# 08_Peripherals.net
KiCad netlist of a schematic drawn in Altium Designer
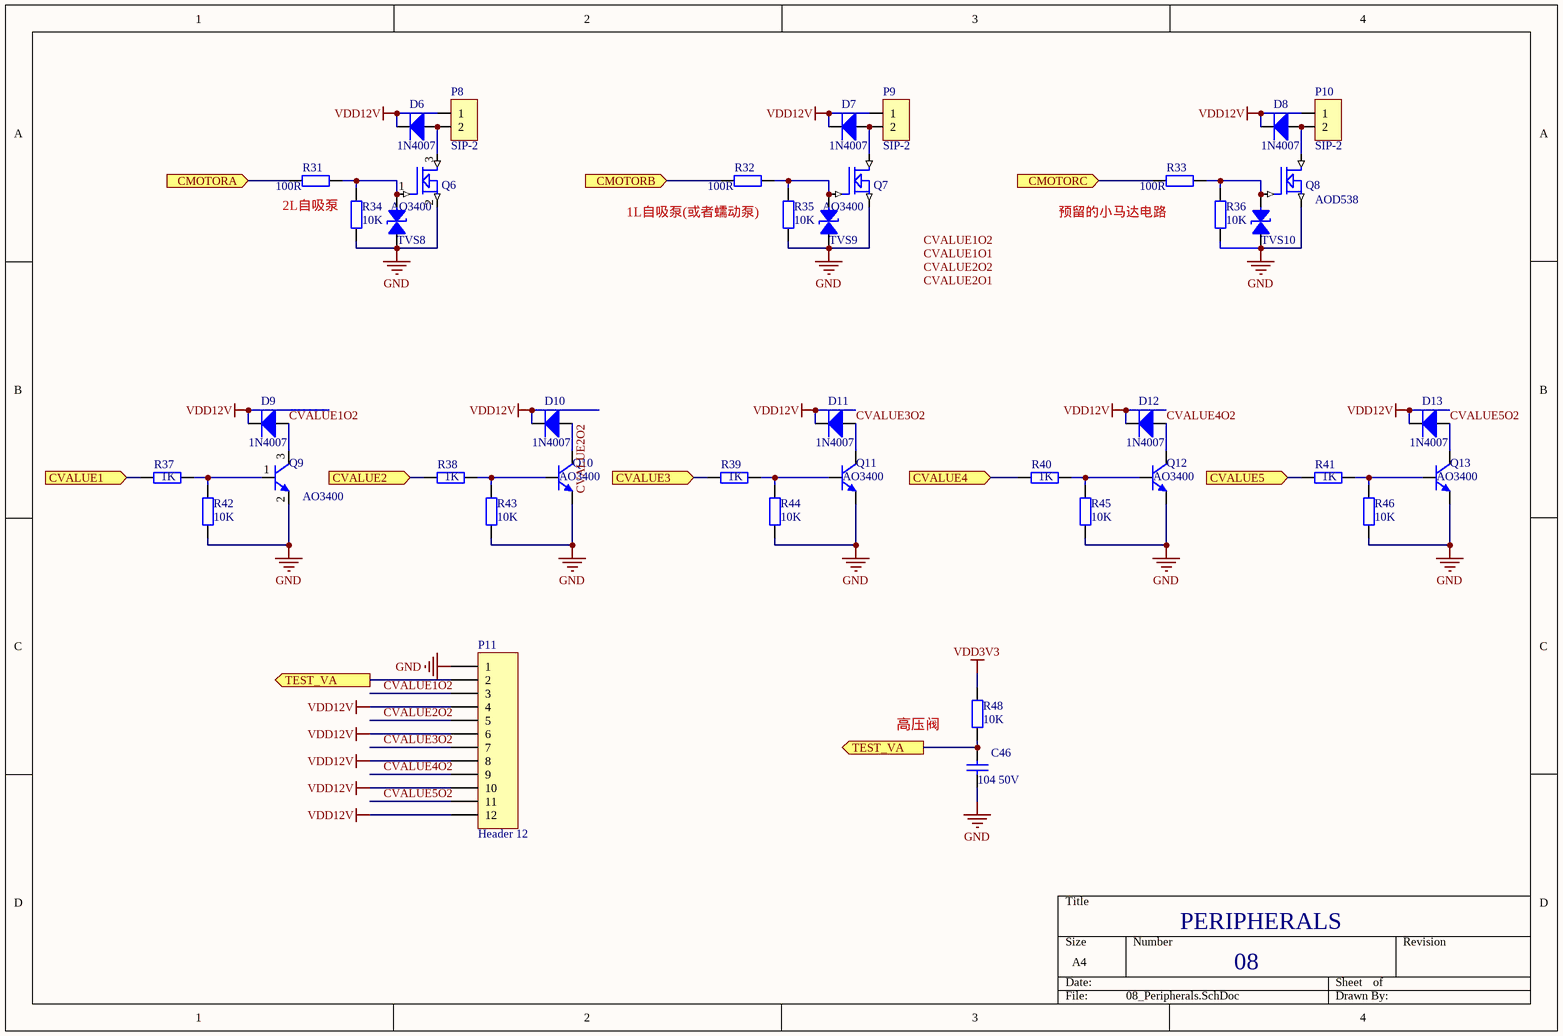
[diagram p0: 08_Peripherals.SchDoc]

(export (version "E")
  (design (tool "Eeschema 10.0.6"))
  (components
    (comp (ref "C46")
      (value "104 50V")
      (footprint "SMD-0603C")
      (description "贴片电容 10%")
      (libsource (lib "XiaoyI") (part "CAP4"))
    )
    (comp (ref "D6")
      (value "1N4007")
      (footprint "DO-214-AC")
      (description "贴片二极管")
      (libsource (lib "XiaoyI") (part "DIODE2"))
    )
    (comp (ref "D7")
      (value "1N4007")
      (footprint "DO-214-AC")
      (description "贴片二极管")
      (libsource (lib "XiaoyI") (part "DIODE2"))
    )
    (comp (ref "D8")
      (value "1N4007")
      (footprint "DO-214-AC")
      (description "贴片二极管")
      (libsource (lib "XiaoyI") (part "DIODE2"))
    )
    (comp (ref "D9")
      (value "1N4007")
      (footprint "DO-214-AC")
      (description "贴片二极管")
      (libsource (lib "XiaoyI") (part "DIODE2"))
    )
    (comp (ref "D10")
      (value "1N4007")
      (footprint "DO-214-AC")
      (description "贴片二极管")
      (libsource (lib "XiaoyI") (part "DIODE2"))
    )
    (comp (ref "D11")
      (value "1N4007")
      (footprint "DO-214-AC")
      (description "贴片二极管")
      (libsource (lib "XiaoyI") (part "DIODE2"))
    )
    (comp (ref "D12")
      (value "1N4007")
      (footprint "DO-214-AC")
      (description "贴片二极管")
      (libsource (lib "XiaoyI") (part "DIODE2"))
    )
    (comp (ref "D13")
      (value "1N4007")
      (footprint "DO-214-AC")
      (description "贴片二极管")
      (libsource (lib "XiaoyI") (part "DIODE2"))
    )
    (comp (ref "P8")
      (value "SIP-2")
      (footprint "SIP-2A")
      (description "XH2.54 2P 立贴")
      (libsource (lib "XiaoyI") (part "SIP-2"))
    )
    (comp (ref "P9")
      (value "SIP-2")
      (footprint "SIP-2A")
      (description "XH2.54 2P 立贴")
      (libsource (lib "XiaoyI") (part "SIP-2"))
    )
    (comp (ref "P10")
      (value "SIP-2")
      (footprint "VH-AW-3.96*2P")
      (description "XH2.54 2P 立贴")
      (libsource (lib "XiaoyI") (part "SIP-2"))
    )
    (comp (ref "P11")
      (value "Header 12")
      (footprint "12X2.54MMZ")
      (description "Header, 12-Pin")
      (fields (field (name "PUBLISHER") "Altium Limited"))
      (libsource (lib "Miscellaneous Connectors") (part "Header 12"))
    )
    (comp (ref "Q6")
      (value "AO3400")
      (footprint "SOT-23")
      (description "MOSFET N")
      (libsource (lib "XiaoyI") (part "MOSFET N"))
    )
    (comp (ref "Q7")
      (value "AO3400")
      (footprint "SOT-23")
      (description "MOSFET N")
      (libsource (lib "") (part "MOSFET N_1"))
    )
    (comp (ref "Q8")
      (value "AOD538")
      (footprint "TO252")
      (description "MOSFET N")
      (libsource (lib "") (part "MOSFET N_1"))
    )
    (comp (ref "Q9")
      (value "AO3400")
      (footprint "SOT-23")
      (description "三极管")
      (libsource (lib "XiaoyI") (part "NPN-1"))
    )
    (comp (ref "Q10")
      (value "AO3400")
      (footprint "SOT-23")
      (description "三极管")
      (libsource (lib "") (part "NPN-1_1"))
    )
    (comp (ref "Q11")
      (value "AO3400")
      (footprint "SOT-23")
      (description "三极管")
      (libsource (lib "") (part "NPN-1_1"))
    )
    (comp (ref "Q12")
      (value "AO3400")
      (footprint "SOT-23")
      (description "三极管")
      (libsource (lib "") (part "NPN-1_1"))
    )
    (comp (ref "Q13")
      (value "AO3400")
      (footprint "SOT-23")
      (description "三极管")
      (libsource (lib "") (part "NPN-1_1"))
    )
    (comp (ref "R31")
      (value "100R")
      (footprint "SMD-0603")
      (description "贴片电阻 5%")
      (libsource (lib "XiaoyI") (part "RES-SOP"))
    )
    (comp (ref "R32")
      (value "100R")
      (footprint "SMD-0603")
      (description "贴片电阻 5%")
      (libsource (lib "XiaoyI") (part "RES-SOP"))
    )
    (comp (ref "R33")
      (value "100R")
      (footprint "SMD-0603")
      (description "贴片电阻 5%")
      (libsource (lib "XiaoyI") (part "RES-SOP"))
    )
    (comp (ref "R34")
      (value "10K")
      (footprint "SMD-0603")
      (description "贴片电阻 5%")
      (libsource (lib "") (part "RES-SOP_1"))
    )
    (comp (ref "R35")
      (value "10K")
      (footprint "SMD-0603")
      (description "贴片电阻 5%")
      (libsource (lib "") (part "RES-SOP_1"))
    )
    (comp (ref "R36")
      (value "10K")
      (footprint "SMD-0603")
      (description "贴片电阻 5%")
      (libsource (lib "") (part "RES-SOP_1"))
    )
    (comp (ref "R37")
      (value "1K")
      (footprint "SMD-0603")
      (description "贴片电阻 5%")
      (libsource (lib "XiaoyI") (part "RES-SOP"))
    )
    (comp (ref "R38")
      (value "1K")
      (footprint "SMD-0603")
      (description "贴片电阻 5%")
      (libsource (lib "XiaoyI") (part "RES-SOP"))
    )
    (comp (ref "R39")
      (value "1K")
      (footprint "SMD-0603")
      (description "贴片电阻 5%")
      (libsource (lib "XiaoyI") (part "RES-SOP"))
    )
    (comp (ref "R40")
      (value "1K")
      (footprint "SMD-0603")
      (description "贴片电阻 5%")
      (libsource (lib "XiaoyI") (part "RES-SOP"))
    )
    (comp (ref "R41")
      (value "1K")
      (footprint "SMD-0603")
      (description "贴片电阻 5%")
      (libsource (lib "XiaoyI") (part "RES-SOP"))
    )
    (comp (ref "R42")
      (value "10K")
      (footprint "SMD-0603")
      (description "贴片电阻 5%")
      (libsource (lib "") (part "RES-SOP_1"))
    )
    (comp (ref "R43")
      (value "10K")
      (footprint "SMD-0603")
      (description "贴片电阻 5%")
      (libsource (lib "") (part "RES-SOP_1"))
    )
    (comp (ref "R44")
      (value "10K")
      (footprint "SMD-0603")
      (description "贴片电阻 5%")
      (libsource (lib "") (part "RES-SOP_1"))
    )
    (comp (ref "R45")
      (value "10K")
      (footprint "SMD-0603")
      (description "贴片电阻 5%")
      (libsource (lib "") (part "RES-SOP_1"))
    )
    (comp (ref "R46")
      (value "10K")
      (footprint "SMD-0603")
      (description "贴片电阻 5%")
      (libsource (lib "") (part "RES-SOP_1"))
    )
    (comp (ref "R48")
      (value "10K")
      (footprint "SMD-0603")
      (description "贴片电阻 5%")
      (libsource (lib "") (part "RES-SOP_2"))
    )
    (comp (ref "TVS8")
      (value "ESD5Z5.0CT1G")
      (footprint "SOD-523")
      (description "TVS")
      (libsource (lib "XiaoyI") (part "TVS-1"))
    )
    (comp (ref "TVS9")
      (value "ESD5Z5.0CT1G")
      (footprint "SOD-523")
      (description "TVS")
      (libsource (lib "XiaoyI") (part "TVS-1"))
    )
    (comp (ref "TVS10")
      (value "ESD5Z5.0CT1G")
      (footprint "SOD-523")
      (description "TVS")
      (libsource (lib "XiaoyI") (part "TVS-1"))
    )
  )
  (nets
    (net (code "1") (name "/CMOTORA") (class "Default")
      (node (ref "R31") (pin "2") (pinfunction "2_2") (pintype "passive"))
    )
    (net (code "2") (name "/CMOTORB") (class "Default")
      (node (ref "R32") (pin "2") (pinfunction "2_2") (pintype "passive"))
    )
    (net (code "3") (name "/CMOTORC") (class "Default")
      (node (ref "R33") (pin "2") (pinfunction "2_2") (pintype "passive"))
    )
    (net (code "4") (name "/CVALUE1") (class "Default")
      (node (ref "R37") (pin "2") (pinfunction "2_2") (pintype "passive"))
    )
    (net (code "6") (name "/CVALUE1O2") (class "Default")
      (node (ref "D9") (pin "1") (pinfunction "A_1") (pintype "passive"))
      (node (ref "P11") (pin "3") (pinfunction "3_3") (pintype "passive"))
      (node (ref "Q9") (pin "3") (pinfunction "C_3") (pintype "passive"))
    )
    (net (code "7") (name "/CVALUE2") (class "Default")
      (node (ref "R38") (pin "2") (pinfunction "2_2") (pintype "passive"))
    )
    (net (code "9") (name "/CVALUE2O2") (class "Default")
      (node (ref "D10") (pin "1") (pinfunction "A_1") (pintype "passive"))
      (node (ref "P11") (pin "5") (pinfunction "5_5") (pintype "passive"))
      (node (ref "Q10") (pin "3") (pinfunction "C_3") (pintype "passive"))
    )
    (net (code "10") (name "/CVALUE3") (class "Default")
      (node (ref "R39") (pin "2") (pinfunction "2_2") (pintype "passive"))
    )
    (net (code "11") (name "/CVALUE3O2") (class "Default")
      (node (ref "D11") (pin "1") (pinfunction "A_1") (pintype "passive"))
      (node (ref "P11") (pin "7") (pinfunction "7_7") (pintype "passive"))
      (node (ref "Q11") (pin "3") (pinfunction "C_3") (pintype "passive"))
    )
    (net (code "12") (name "/CVALUE4") (class "Default")
      (node (ref "R40") (pin "2") (pinfunction "2_2") (pintype "passive"))
    )
    (net (code "13") (name "/CVALUE4O2") (class "Default")
      (node (ref "D12") (pin "1") (pinfunction "A_1") (pintype "passive"))
      (node (ref "P11") (pin "9") (pinfunction "9_9") (pintype "passive"))
      (node (ref "Q12") (pin "3") (pinfunction "C_3") (pintype "passive"))
    )
    (net (code "14") (name "/CVALUE5") (class "Default")
      (node (ref "R41") (pin "2") (pinfunction "2_2") (pintype "passive"))
    )
    (net (code "15") (name "/CVALUE5O2") (class "Default")
      (node (ref "D13") (pin "1") (pinfunction "A_1") (pintype "passive"))
      (node (ref "P11") (pin "11") (pinfunction "11_11") (pintype "passive"))
      (node (ref "Q13") (pin "3") (pinfunction "C_3") (pintype "passive"))
    )
    (net (code "16") (name "/TEST_VA") (class "Default")
      (node (ref "C46") (pin "2") (pinfunction "2_2") (pintype "passive"))
      (node (ref "P11") (pin "2") (pinfunction "2_2") (pintype "passive"))
      (node (ref "R48") (pin "1") (pinfunction "1_1") (pintype "passive"))
    )
    (net (code "17") (name "GND") (class "Default")
      (node (ref "C46") (pin "1") (pinfunction "1_1") (pintype "passive"))
      (node (ref "P11") (pin "1") (pinfunction "1_1") (pintype "passive"))
      (node (ref "Q10") (pin "2") (pinfunction "E_2") (pintype "passive"))
      (node (ref "Q11") (pin "2") (pinfunction "E_2") (pintype "passive"))
      (node (ref "Q12") (pin "2") (pinfunction "E_2") (pintype "passive"))
      (node (ref "Q13") (pin "2") (pinfunction "E_2") (pintype "passive"))
      (node (ref "Q6") (pin "2") (pinfunction "S_2") (pintype "output"))
      (node (ref "Q7") (pin "2") (pinfunction "S_2") (pintype "output"))
      (node (ref "Q8") (pin "2") (pinfunction "S_2") (pintype "output"))
      (node (ref "Q9") (pin "2") (pinfunction "E_2") (pintype "passive"))
      (node (ref "R34") (pin "2") (pinfunction "2_2") (pintype "passive"))
      (node (ref "R35") (pin "2") (pinfunction "2_2") (pintype "passive"))
      (node (ref "R36") (pin "2") (pinfunction "2_2") (pintype "passive"))
      (node (ref "R42") (pin "2") (pinfunction "2_2") (pintype "passive"))
      (node (ref "R43") (pin "2") (pinfunction "2_2") (pintype "passive"))
      (node (ref "R44") (pin "2") (pinfunction "2_2") (pintype "passive"))
      (node (ref "R45") (pin "2") (pinfunction "2_2") (pintype "passive"))
      (node (ref "R46") (pin "2") (pinfunction "2_2") (pintype "passive"))
      (node (ref "TVS10") (pin "1") (pinfunction "A_1") (pintype "passive"))
      (node (ref "TVS8") (pin "1") (pinfunction "A_1") (pintype "passive"))
      (node (ref "TVS9") (pin "1") (pinfunction "A_1") (pintype "passive"))
    )
    (net (code "18") (name "Net-(D6-A)") (class "Default")
      (node (ref "D6") (pin "1") (pinfunction "A_1") (pintype "passive"))
      (node (ref "P8") (pin "2") (pinfunction "2_2") (pintype "passive"))
      (node (ref "Q6") (pin "3") (pinfunction "D_3") (pintype "input"))
    )
    (net (code "19") (name "Net-(D7-A)") (class "Default")
      (node (ref "D7") (pin "1") (pinfunction "A_1") (pintype "passive"))
      (node (ref "P9") (pin "2") (pinfunction "2_2") (pintype "passive"))
      (node (ref "Q7") (pin "3") (pinfunction "D_3") (pintype "input"))
    )
    (net (code "20") (name "Net-(D8-A)") (class "Default")
      (node (ref "D8") (pin "1") (pinfunction "A_1") (pintype "passive"))
      (node (ref "P10") (pin "2") (pinfunction "2_2") (pintype "passive"))
      (node (ref "Q8") (pin "3") (pinfunction "D_3") (pintype "input"))
    )
    (net (code "21") (name "Net-(Q6-G)") (class "Default")
      (node (ref "Q6") (pin "1") (pinfunction "G_1") (pintype "input"))
      (node (ref "R31") (pin "1") (pinfunction "1_1") (pintype "passive"))
      (node (ref "R34") (pin "1") (pinfunction "1_1") (pintype "passive"))
      (node (ref "TVS8") (pin "2") (pinfunction "B_2") (pintype "passive"))
    )
    (net (code "22") (name "Net-(Q7-G)") (class "Default")
      (node (ref "Q7") (pin "1") (pinfunction "G_1") (pintype "input"))
      (node (ref "R32") (pin "1") (pinfunction "1_1") (pintype "passive"))
      (node (ref "R35") (pin "1") (pinfunction "1_1") (pintype "passive"))
      (node (ref "TVS9") (pin "2") (pinfunction "B_2") (pintype "passive"))
    )
    (net (code "23") (name "Net-(Q8-G)") (class "Default")
      (node (ref "Q8") (pin "1") (pinfunction "G_1") (pintype "input"))
      (node (ref "R33") (pin "1") (pinfunction "1_1") (pintype "passive"))
      (node (ref "R36") (pin "1") (pinfunction "1_1") (pintype "passive"))
      (node (ref "TVS10") (pin "2") (pinfunction "B_2") (pintype "passive"))
    )
    (net (code "24") (name "Net-(Q9-B)") (class "Default")
      (node (ref "Q9") (pin "1") (pinfunction "B_1") (pintype "passive"))
      (node (ref "R37") (pin "1") (pinfunction "1_1") (pintype "passive"))
      (node (ref "R42") (pin "1") (pinfunction "1_1") (pintype "passive"))
    )
    (net (code "25") (name "Net-(Q10-B)") (class "Default")
      (node (ref "Q10") (pin "1") (pinfunction "B_1") (pintype "passive"))
      (node (ref "R38") (pin "1") (pinfunction "1_1") (pintype "passive"))
      (node (ref "R43") (pin "1") (pinfunction "1_1") (pintype "passive"))
    )
    (net (code "26") (name "Net-(Q11-B)") (class "Default")
      (node (ref "Q11") (pin "1") (pinfunction "B_1") (pintype "passive"))
      (node (ref "R39") (pin "1") (pinfunction "1_1") (pintype "passive"))
      (node (ref "R44") (pin "1") (pinfunction "1_1") (pintype "passive"))
    )
    (net (code "27") (name "Net-(Q12-B)") (class "Default")
      (node (ref "Q12") (pin "1") (pinfunction "B_1") (pintype "passive"))
      (node (ref "R40") (pin "1") (pinfunction "1_1") (pintype "passive"))
      (node (ref "R45") (pin "1") (pinfunction "1_1") (pintype "passive"))
    )
    (net (code "28") (name "Net-(Q13-B)") (class "Default")
      (node (ref "Q13") (pin "1") (pinfunction "B_1") (pintype "passive"))
      (node (ref "R41") (pin "1") (pinfunction "1_1") (pintype "passive"))
      (node (ref "R46") (pin "1") (pinfunction "1_1") (pintype "passive"))
    )
    (net (code "29") (name "VDD3V3") (class "Default")
      (node (ref "R48") (pin "2") (pinfunction "2_2") (pintype "passive"))
    )
    (net (code "30") (name "VDD12V") (class "Default")
      (node (ref "D10") (pin "2") (pinfunction "K_2") (pintype "passive"))
      (node (ref "D11") (pin "2") (pinfunction "K_2") (pintype "passive"))
      (node (ref "D12") (pin "2") (pinfunction "K_2") (pintype "passive"))
      (node (ref "D13") (pin "2") (pinfunction "K_2") (pintype "passive"))
      (node (ref "D6") (pin "2") (pinfunction "K_2") (pintype "passive"))
      (node (ref "D7") (pin "2") (pinfunction "K_2") (pintype "passive"))
      (node (ref "D8") (pin "2") (pinfunction "K_2") (pintype "passive"))
      (node (ref "D9") (pin "2") (pinfunction "K_2") (pintype "passive"))
      (node (ref "P10") (pin "1") (pinfunction "1_1") (pintype "passive"))
      (node (ref "P11") (pin "10") (pinfunction "10_10") (pintype "passive"))
      (node (ref "P11") (pin "12") (pinfunction "12_12") (pintype "passive"))
      (node (ref "P11") (pin "4") (pinfunction "4_4") (pintype "passive"))
      (node (ref "P11") (pin "6") (pinfunction "6_6") (pintype "passive"))
      (node (ref "P11") (pin "8") (pinfunction "8_8") (pintype "passive"))
      (node (ref "P8") (pin "1") (pinfunction "1_1") (pintype "passive"))
      (node (ref "P9") (pin "1") (pinfunction "1_1") (pintype "passive"))
    )
  )
)
